# STM32_microcontroller_power.net
KiCad netlist of a schematic drawn in Altium Designer
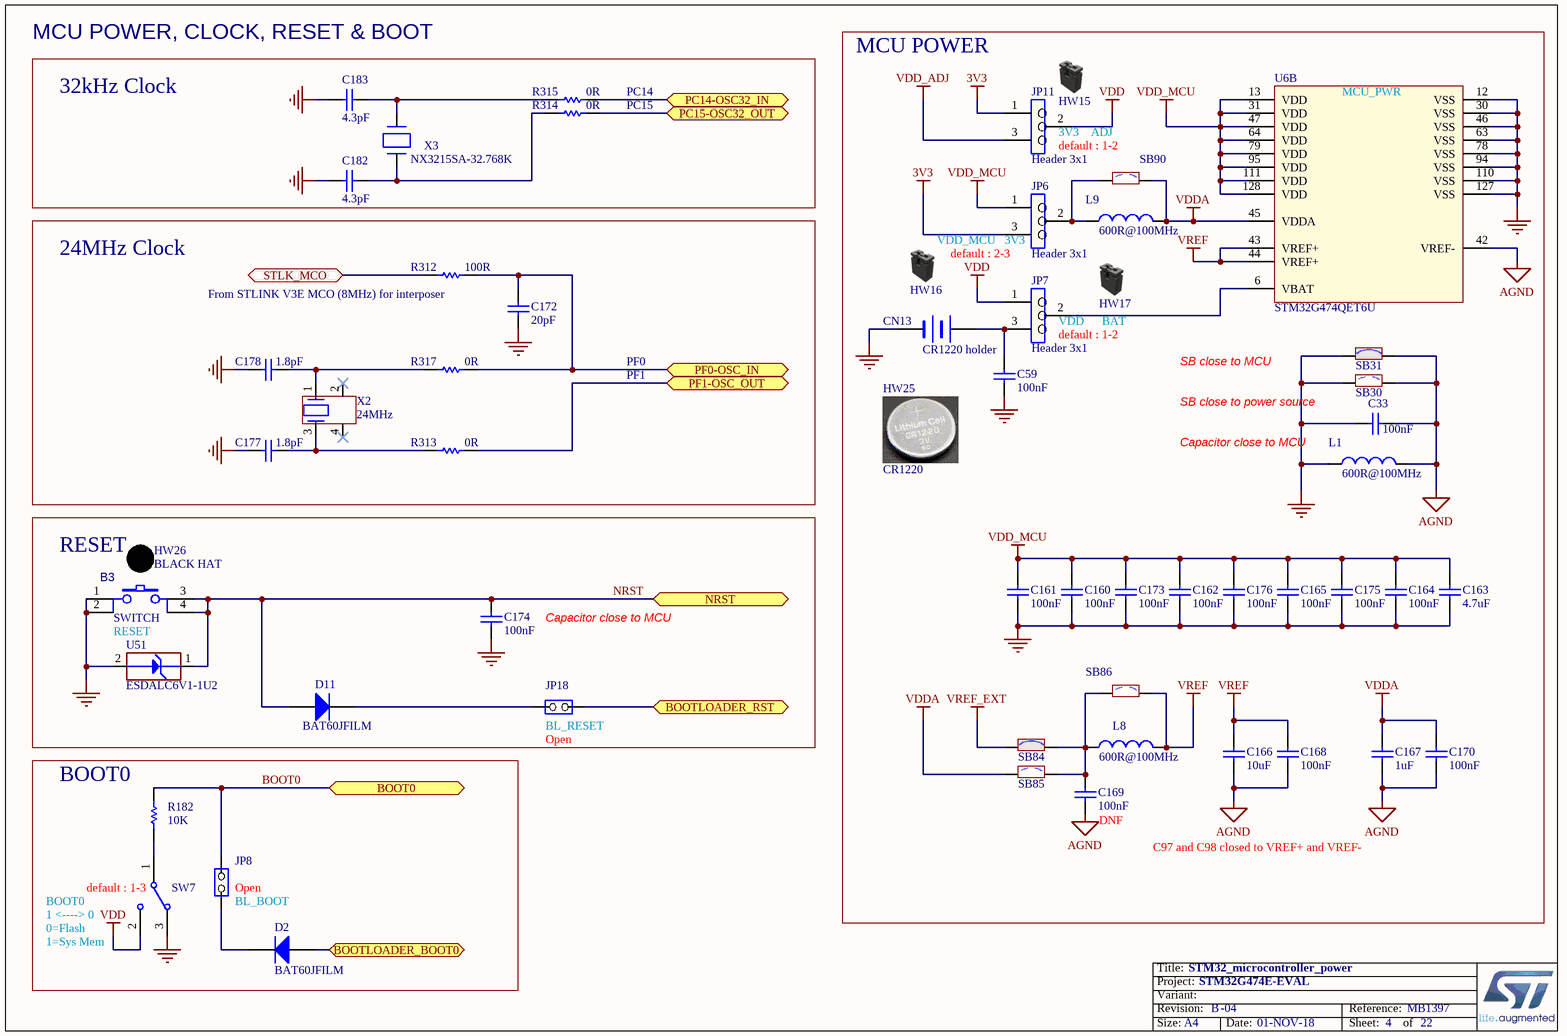
[diagram p0: STM32_microcontroller_power.SchDoc]

(export (version "E")
  (design (tool "Eeschema 10.0.6"))
  (components
    (comp (ref "B3")
      (value "SWITCH")
      (footprint "SWI_WEALTHMETAL_TD-0341_4P_BLACK")
      (description "Non-Open Push-Button 0.1A 24V BLACK")
      (fields
        (field (name "INTERNAL_PART_NUMBER") "MCD-00001")
        (field (name "MANUFACTURER_PART_NUMBER") "TD-0341")
        (field (name "PROVIDED_BY") "SUBCO")
      )
      (libsource (lib "MCD_PARTS_database") (part "SW-PUSH-CMS"))
    )
    (comp (ref "C33")
      (value "100nF")
      (footprint "C0402")
      (description "Capacitor, MLCC, 100nF, 16V, X7R, 10%, 0402, T=0.5mm")
      (fields
        (field (name "INTERNAL_PART_NUMBER") "MCD-00006")
        (field (name "MANUFACTURER_PART_NUMBER") "CC0402KRX7R7BB104")
        (field (name "PROVIDED_BY") "SUBCO")
      )
      (libsource (lib "MCD_PARTS_database") (part "Capacitor"))
    )
    (comp (ref "C59")
      (value "100nF")
      (footprint "C0402")
      (description "Capacitor, MLCC, 100nF, 16V, X7R, 10%, 0402, T=0.5mm")
      (fields
        (field (name "INTERNAL_PART_NUMBER") "MCD-00006")
        (field (name "MANUFACTURER_PART_NUMBER") "CC0402KRX7R7BB104")
        (field (name "PROVIDED_BY") "SUBCO")
      )
      (libsource (lib "MCD_PARTS_database") (part "Capacitor"))
    )
    (comp (ref "C160")
      (value "100nF")
      (footprint "C0402")
      (description "Capacitor, MLCC, 100nF, 16V, X7R, 10%, 0402, T=0.5mm")
      (fields
        (field (name "INTERNAL_PART_NUMBER") "MCD-00006")
        (field (name "MANUFACTURER_PART_NUMBER") "CC0402KRX7R7BB104")
        (field (name "PROVIDED_BY") "SUBCO")
      )
      (libsource (lib "MCD_PARTS_database") (part "Capacitor"))
    )
    (comp (ref "C161")
      (value "100nF")
      (footprint "C0402")
      (description "Capacitor, MLCC, 100nF, 16V, X7R, 10%, 0402, T=0.5mm")
      (fields
        (field (name "INTERNAL_PART_NUMBER") "MCD-00006")
        (field (name "MANUFACTURER_PART_NUMBER") "CC0402KRX7R7BB104")
        (field (name "PROVIDED_BY") "SUBCO")
      )
      (libsource (lib "MCD_PARTS_database") (part "Capacitor"))
    )
    (comp (ref "C162")
      (value "100nF")
      (footprint "C0402")
      (description "Capacitor, MLCC, 100nF, 16V, X7R, 10%, 0402, T=0.5mm")
      (fields
        (field (name "INTERNAL_PART_NUMBER") "MCD-00006")
        (field (name "MANUFACTURER_PART_NUMBER") "CC0402KRX7R7BB104")
        (field (name "PROVIDED_BY") "SUBCO")
      )
      (libsource (lib "MCD_PARTS_database") (part "Capacitor"))
    )
    (comp (ref "C163")
      (value "4.7uF")
      (footprint "C0603")
      (description "Capacitor, MLCC, 4.7uF, 16V, X5R, 10%, 0603, T=0.8mm")
      (fields
        (field (name "INTERNAL_PART_NUMBER") "MCD-00009")
        (field (name "MANUFACTURER_PART_NUMBER") "CC0603KRX5R7BB475")
        (field (name "PROVIDED_BY") "SUBCO")
      )
      (libsource (lib "MCD_PARTS_database") (part "Capacitor"))
    )
    (comp (ref "C164")
      (value "100nF")
      (footprint "C0402")
      (description "Capacitor, MLCC, 100nF, 16V, X7R, 10%, 0402, T=0.5mm")
      (fields
        (field (name "INTERNAL_PART_NUMBER") "MCD-00006")
        (field (name "MANUFACTURER_PART_NUMBER") "CC0402KRX7R7BB104")
        (field (name "PROVIDED_BY") "SUBCO")
      )
      (libsource (lib "MCD_PARTS_database") (part "Capacitor"))
    )
    (comp (ref "C165")
      (value "100nF")
      (footprint "C0402")
      (description "Capacitor, MLCC, 100nF, 16V, X7R, 10%, 0402, T=0.5mm")
      (fields
        (field (name "INTERNAL_PART_NUMBER") "MCD-00006")
        (field (name "MANUFACTURER_PART_NUMBER") "CC0402KRX7R7BB104")
        (field (name "PROVIDED_BY") "SUBCO")
      )
      (libsource (lib "MCD_PARTS_database") (part "Capacitor"))
    )
    (comp (ref "C166")
      (value "10uF")
      (footprint "C0805")
      (description "Capacitor, MLCC, 10uF, 25V, X5R, 10%, 0805, T=0,85mm")
      (fields
        (field (name "INTERNAL_PART_NUMBER") "MCD-00014")
        (field (name "MANUFACTURER_PART_NUMBER") "CC0805KRX5R8BB106")
        (field (name "PROVIDED_BY") "SUBCO")
      )
      (libsource (lib "MCD_PARTS_database") (part "Capacitor"))
    )
    (comp (ref "C167")
      (value "1uF")
      (footprint "C0603")
      (description "Capacitor, MLCC, 1uF, 16V, X5R, 10%, 0603, T=0,8mm")
      (fields
        (field (name "INTERNAL_PART_NUMBER") "MCD-00010")
        (field (name "MANUFACTURER_PART_NUMBER") "CC0603KRX5R7BB105")
        (field (name "PROVIDED_BY") "SUBCO")
      )
      (libsource (lib "MCD_PARTS_database") (part "Capacitor"))
    )
    (comp (ref "C168")
      (value "100nF")
      (footprint "C0402")
      (description "Capacitor, MLCC, 100nF, 16V, X7R, 10%, 0402, T=0.5mm")
      (fields
        (field (name "INTERNAL_PART_NUMBER") "MCD-00006")
        (field (name "MANUFACTURER_PART_NUMBER") "CC0402KRX7R7BB104")
        (field (name "PROVIDED_BY") "SUBCO")
      )
      (libsource (lib "MCD_PARTS_database") (part "Capacitor"))
    )
    (comp (ref "C169")
      (value "100nF")
      (footprint "C0402")
      (description "Capacitor, MLCC, 100nF, 16V, X7R, 10%, 0402, T=0.5mm")
      (fields
        (field (name "INTERNAL_PART_NUMBER") "MCD-00006")
        (field (name "MANUFACTURER_PART_NUMBER") "CC0402KRX7R7BB104")
        (field (name "PROVIDED_BY") "SUBCO")
      )
      (libsource (lib "MCD_PARTS_database") (part "Capacitor"))
    )
    (comp (ref "C170")
      (value "100nF")
      (footprint "C0402")
      (description "Capacitor, MLCC, 100nF, 16V, X7R, 10%, 0402, T=0.5mm")
      (fields
        (field (name "INTERNAL_PART_NUMBER") "MCD-00006")
        (field (name "MANUFACTURER_PART_NUMBER") "CC0402KRX7R7BB104")
        (field (name "PROVIDED_BY") "SUBCO")
      )
      (libsource (lib "MCD_PARTS_database") (part "Capacitor"))
    )
    (comp (ref "C172")
      (value "20pF")
      (footprint "C0402")
      (description "Capacitor, MLCC, 20pF, 50V, NPO, 5%, 0402, T=0,5mm")
      (fields
        (field (name "INTERNAL_PART_NUMBER") "MCD-00016")
        (field (name "MANUFACTURER_PART_NUMBER") "CC0402JRNPO9BN200")
        (field (name "PROVIDED_BY") "SUBCO")
      )
      (libsource (lib "MCD_PARTS_database") (part "Capacitor"))
    )
    (comp (ref "C173")
      (value "100nF")
      (footprint "C0402")
      (description "Capacitor, MLCC, 100nF, 16V, X7R, 10%, 0402, T=0.5mm")
      (fields
        (field (name "INTERNAL_PART_NUMBER") "MCD-00006")
        (field (name "MANUFACTURER_PART_NUMBER") "CC0402KRX7R7BB104")
        (field (name "PROVIDED_BY") "SUBCO")
      )
      (libsource (lib "MCD_PARTS_database") (part "Capacitor"))
    )
    (comp (ref "C174")
      (value "100nF")
      (footprint "C0402")
      (description "Capacitor, MLCC, 100nF, 16V, X7R, 10%, 0402, T=0.5mm")
      (fields
        (field (name "INTERNAL_PART_NUMBER") "MCD-00006")
        (field (name "MANUFACTURER_PART_NUMBER") "CC0402KRX7R7BB104")
        (field (name "PROVIDED_BY") "SUBCO")
      )
      (libsource (lib "MCD_PARTS_database") (part "Capacitor"))
    )
    (comp (ref "C175")
      (value "100nF")
      (footprint "C0402")
      (description "Capacitor, MLCC, 100nF, 16V, X7R, 10%, 0402, T=0.5mm")
      (fields
        (field (name "INTERNAL_PART_NUMBER") "MCD-00006")
        (field (name "MANUFACTURER_PART_NUMBER") "CC0402KRX7R7BB104")
        (field (name "PROVIDED_BY") "SUBCO")
      )
      (libsource (lib "MCD_PARTS_database") (part "Capacitor"))
    )
    (comp (ref "C176")
      (value "100nF")
      (footprint "C0402")
      (description "Capacitor, MLCC, 100nF, 16V, X7R, 10%, 0402, T=0.5mm")
      (fields
        (field (name "INTERNAL_PART_NUMBER") "MCD-00006")
        (field (name "MANUFACTURER_PART_NUMBER") "CC0402KRX7R7BB104")
        (field (name "PROVIDED_BY") "SUBCO")
      )
      (libsource (lib "MCD_PARTS_database") (part "Capacitor"))
    )
    (comp (ref "C177")
      (value "1.8pF")
      (footprint "C0402")
      (description "Capacitor, MLCC, 1.8pF, 50V, NPO, +-0.25pF, 0402, T=0,5mm")
      (fields
        (field (name "INTERNAL_PART_NUMBER") "MCD-01598")
        (field (name "MANUFACTURER_PART_NUMBER") "CC0402CRNPO9BN1R8")
        (field (name "PROVIDED_BY") "SUBCO")
      )
      (libsource (lib "MCD_PARTS_database") (part "Capacitor"))
    )
    (comp (ref "C178")
      (value "1.8pF")
      (footprint "C0402")
      (description "Capacitor, MLCC, 1.8pF, 50V, NPO, +-0.25pF, 0402, T=0,5mm")
      (fields
        (field (name "INTERNAL_PART_NUMBER") "MCD-01598")
        (field (name "MANUFACTURER_PART_NUMBER") "CC0402CRNPO9BN1R8")
        (field (name "PROVIDED_BY") "SUBCO")
      )
      (libsource (lib "MCD_PARTS_database") (part "Capacitor"))
    )
    (comp (ref "C182")
      (value "4.3pF")
      (footprint "C0402")
      (description "Capacitor, MLCC, 4.3pF, 50V, NPO, +-0.25pF, 0402, T=0,5mm")
      (fields
        (field (name "INTERNAL_PART_NUMBER") "MCD-01706")
        (field (name "MANUFACTURER_PART_NUMBER") "CC0402CRNPO9BN4R3")
        (field (name "PROVIDED_BY") "SUBCO")
      )
      (libsource (lib "MCD_PARTS_database") (part "Capacitor"))
    )
    (comp (ref "C183")
      (value "4.3pF")
      (footprint "C0402")
      (description "Capacitor, MLCC, 4.3pF, 50V, NPO, +-0.25pF, 0402, T=0,5mm")
      (fields
        (field (name "INTERNAL_PART_NUMBER") "MCD-01706")
        (field (name "MANUFACTURER_PART_NUMBER") "CC0402CRNPO9BN4R3")
        (field (name "PROVIDED_BY") "SUBCO")
      )
      (libsource (lib "MCD_PARTS_database") (part "Capacitor"))
    )
    (comp (ref "CN13")
      (value "CR1220 holder")
      (footprint "BAT_HARWIN_S8411-45R_SMD_2P")
      (description "Battery Coin Cell holder, CR1220_12mm, Height 4.25mm")
      (fields
        (field (name "INTERNAL_PART_NUMBER") "MCD-00558")
        (field (name "MANUFACTURER_PART_NUMBER") "S8411-45R")
        (field (name "PROVIDED_BY") "SUBCO")
      )
      (libsource (lib "MCD_PARTS_database") (part "BATTERY HOLDER"))
    )
    (comp (ref "D2")
      (value "BAT60JFILM")
      (footprint "DIO_SOD323")
      (fields
        (field (name "INTERNAL_PART_NUMBER") "MCD-00034")
        (field (name "MANUFACTURER") "STMICROELECTRONICS")
        (field (name "BMS_PART_NUMBER") "9151097")
        (field (name "PROVIDED_BY") "SUBCO with ST control")
      )
      (libsource (lib "MCD_PARTS_database") (part "BAT60JFILM"))
    )
    (comp (ref "D11")
      (value "BAT60JFILM")
      (footprint "DIO_SOD323")
      (fields
        (field (name "INTERNAL_PART_NUMBER") "MCD-00034")
        (field (name "MANUFACTURER") "STMICROELECTRONICS")
        (field (name "BMS_PART_NUMBER") "9151097")
        (field (name "PROVIDED_BY") "SUBCO with ST control")
      )
      (libsource (lib "MCD_PARTS_database") (part "BAT60JFILM"))
    )
    (comp (ref "HW15")
      (value "Shunt Black 2.54mm")
      (description "SHUNT 2.54mm BLACK")
      (fields
        (field (name "INTERNAL_PART_NUMBER") "MCD-00043")
        (field (name "MANUFACTURER_PART_NUMBER") "SNT-100-BK-G")
        (field (name "PROVIDED_BY") "SUBCO")
      )
      (libsource (lib "MCD_PARTS_database") (part "Shunt Black 2.54mm"))
    )
    (comp (ref "HW16")
      (value "Shunt Black 2.54mm")
      (description "SHUNT 2.54mm BLACK")
      (fields
        (field (name "INTERNAL_PART_NUMBER") "MCD-00043")
        (field (name "MANUFACTURER_PART_NUMBER") "SNT-100-BK-G")
        (field (name "PROVIDED_BY") "SUBCO")
      )
      (libsource (lib "MCD_PARTS_database") (part "Shunt Black 2.54mm"))
    )
    (comp (ref "HW17")
      (value "Shunt Black 2.54mm")
      (description "SHUNT 2.54mm BLACK")
      (fields
        (field (name "INTERNAL_PART_NUMBER") "MCD-00043")
        (field (name "MANUFACTURER_PART_NUMBER") "SNT-100-BK-G")
        (field (name "PROVIDED_BY") "SUBCO")
      )
      (libsource (lib "MCD_PARTS_database") (part "Shunt Black 2.54mm"))
    )
    (comp (ref "HW25")
      (value "CR1220")
      (description "Battery Back-Up CR1220,3V,12X2.0MM,35mA")
      (fields
        (field (name "INTERNAL_PART_NUMBER") "MCD-01197")
        (field (name "MANUFACTURER") "tbd")
        (field (name "PROVIDED_BY") "SUBCO")
      )
      (libsource (lib "MCD_PARTS_database") (part "BBU_CR1220"))
    )
    (comp (ref "HW26")
      (value "BLACK HAT")
      (description "Black Hat for switch TD0341X-G01-BLA")
      (fields
        (field (name "INTERNAL_PART_NUMBER") "MCD-00635")
        (field (name "MANUFACTURER_PART_NUMBER") "988.16.09.3.00003_SH-517")
        (field (name "PROVIDED_BY") "SUBCO")
      )
      (libsource (lib "MCD_PARTS_database") (part "BUTTON_HAT_BLACK"))
    )
    (comp (ref "JP6")
      (value "Header 3x1")
      (footprint "CON_SAMTEC_TSW-103-07-F-S")
      (description "Header, 3x1, 2,54mm, VR, TH, Height 5.84mm/2.54mm")
      (fields
        (field (name "INTERNAL_PART_NUMBER") "MCD-00111")
        (field (name "MANUFACTURER_PART_NUMBER") "TSW-103-07-F-S")
        (field (name "PROVIDED_BY") "SUBCO")
      )
      (libsource (lib "MCD_PARTS_database") (part "Jumper_Header 3x1"))
    )
    (comp (ref "JP7")
      (value "Header 3x1")
      (footprint "CON_SAMTEC_TSW-103-07-F-S")
      (description "Header, 3x1, 2,54mm, VR, TH, Height 5.84mm/2.54mm")
      (fields
        (field (name "INTERNAL_PART_NUMBER") "MCD-00111")
        (field (name "MANUFACTURER_PART_NUMBER") "TSW-103-07-F-S")
        (field (name "PROVIDED_BY") "SUBCO")
      )
      (libsource (lib "MCD_PARTS_database") (part "Jumper_Header 3x1"))
    )
    (comp (ref "JP8")
      (value "Jumper_Header 2x1")
      (footprint "CON_SAMTEC_TSW-102-07-G-S")
      (description "Header, 2x1, 2,54mm, VR, TH, Height 5.84mm/2.54mm")
      (fields
        (field (name "INTERNAL_PART_NUMBER") "MCD-00045")
        (field (name "MANUFACTURER_PART_NUMBER") "TSW-102-07-x-S")
        (field (name "PROVIDED_BY") "SUBCO")
      )
      (libsource (lib "MCD_PARTS_database") (part "Jumper_Header 2x1"))
    )
    (comp (ref "JP11")
      (value "Header 3x1")
      (footprint "CON_SAMTEC_TSW-103-07-F-S")
      (description "Header, 3x1, 2,54mm, VR, TH, Height 5.84mm/2.54mm")
      (fields
        (field (name "INTERNAL_PART_NUMBER") "MCD-00111")
        (field (name "MANUFACTURER_PART_NUMBER") "TSW-103-07-F-S")
        (field (name "PROVIDED_BY") "SUBCO")
      )
      (libsource (lib "MCD_PARTS_database") (part "Jumper_Header 3x1"))
    )
    (comp (ref "JP18")
      (value "Jumper_Header 2x1")
      (footprint "CON_SAMTEC_TSW-102-07-G-S")
      (description "Header, 2x1, 2,54mm, VR, TH, Height 5.84mm/2.54mm")
      (fields
        (field (name "INTERNAL_PART_NUMBER") "MCD-00045")
        (field (name "MANUFACTURER_PART_NUMBER") "TSW-102-07-x-S")
        (field (name "PROVIDED_BY") "SUBCO")
      )
      (libsource (lib "MCD_PARTS_database") (part "Jumper_Header 2x1"))
    )
    (comp (ref "L1")
      (value "600R@100MHz")
      (footprint "L0603")
      (description "SMD Chip ferrite bead, 600R@100MHz +/-25%, 350mA, 500mohm DC, 0603, T=0.8mm")
      (fields
        (field (name "INTERNAL_PART_NUMBER") "MCD-00047")
        (field (name "MANUFACTURER_PART_NUMBER") "FCM1608KF-601T03")
        (field (name "PROVIDED_BY") "SUBCO")
      )
      (libsource (lib "MCD_PARTS_database") (part "BEAD"))
    )
    (comp (ref "L8")
      (value "600R@100MHz")
      (footprint "L0603")
      (description "SMD Chip ferrite bead, 600R@100MHz +/-25%, 350mA, 500mohm DC, 0603, T=0.8mm")
      (fields
        (field (name "INTERNAL_PART_NUMBER") "MCD-00047")
        (field (name "MANUFACTURER_PART_NUMBER") "FCM1608KF-601T03")
        (field (name "PROVIDED_BY") "SUBCO")
      )
      (libsource (lib "MCD_PARTS_database") (part "BEAD"))
    )
    (comp (ref "L9")
      (value "600R@100MHz")
      (footprint "L0603")
      (description "SMD Chip ferrite bead, 600R@100MHz +/-25%, 350mA, 500mohm DC, 0603, T=0.8mm")
      (fields
        (field (name "INTERNAL_PART_NUMBER") "MCD-00047")
        (field (name "MANUFACTURER_PART_NUMBER") "FCM1608KF-601T03")
        (field (name "PROVIDED_BY") "SUBCO")
      )
      (libsource (lib "MCD_PARTS_database") (part "BEAD"))
    )
    (comp (ref "R182")
      (value "10K")
      (footprint "R0402")
      (description "Resistor,10K,0402,1%,1/16W")
      (fields
        (field (name "INTERNAL_PART_NUMBER") "MCD-00053")
        (field (name "MANUFACTURER_PART_NUMBER") "RC0402FR-0710KL")
        (field (name "PROVIDED_BY") "SUBCO")
      )
      (libsource (lib "MCD_PARTS_database") (part "Resistor"))
    )
    (comp (ref "R312")
      (value "100R")
      (footprint "R0402")
      (description "Resistor,100R,0402,1%,1/16W")
      (fields
        (field (name "INTERNAL_PART_NUMBER") "MCD-00119")
        (field (name "MANUFACTURER_PART_NUMBER") "RC0402FR-07100RL")
        (field (name "PROVIDED_BY") "SUBCO")
      )
      (libsource (lib "MCD_PARTS_database") (part "Resistor"))
    )
    (comp (ref "R313")
      (value "0R")
      (footprint "R0402")
      (description "Resistor,0R,0402,5%,1/16W")
      (fields
        (field (name "INTERNAL_PART_NUMBER") "MCD-00052")
        (field (name "MANUFACTURER_PART_NUMBER") "RC0402JR-070RL")
        (field (name "PROVIDED_BY") "SUBCO")
      )
      (libsource (lib "MCD_PARTS_database") (part "Resistor"))
    )
    (comp (ref "R314")
      (value "0R")
      (footprint "R0402")
      (description "Resistor,0R,0402,5%,1/16W")
      (fields
        (field (name "INTERNAL_PART_NUMBER") "MCD-00052")
        (field (name "MANUFACTURER_PART_NUMBER") "RC0402JR-070RL")
        (field (name "PROVIDED_BY") "SUBCO")
      )
      (libsource (lib "MCD_PARTS_database") (part "Resistor"))
    )
    (comp (ref "R315")
      (value "0R")
      (footprint "R0402")
      (description "Resistor,0R,0402,5%,1/16W")
      (fields
        (field (name "INTERNAL_PART_NUMBER") "MCD-00052")
        (field (name "MANUFACTURER_PART_NUMBER") "RC0402JR-070RL")
        (field (name "PROVIDED_BY") "SUBCO")
      )
      (libsource (lib "MCD_PARTS_database") (part "Resistor"))
    )
    (comp (ref "R317")
      (value "0R")
      (footprint "R0402")
      (description "Resistor,0R,0402,5%,1/16W")
      (fields
        (field (name "INTERNAL_PART_NUMBER") "MCD-00052")
        (field (name "MANUFACTURER_PART_NUMBER") "RC0402JR-070RL")
        (field (name "PROVIDED_BY") "SUBCO")
      )
      (libsource (lib "MCD_PARTS_database") (part "Resistor"))
    )
    (comp (ref "SB30")
      (value "SB_OFF")
      (footprint "SOLDER-BRIDGE_R0603-0R")
      (description "Solder Bridge OFF")
      (fields
        (field (name "INTERNAL_PART_NUMBER") "MCD-00072")
        (field (name "MANUFACTURER_PART_NUMBER") "RC0603JR-070RL")
        (field (name "PROVIDED_BY") "SUBCO")
      )
      (libsource (lib "MCD_PARTS_database") (part "SB_OFF"))
    )
    (comp (ref "SB31")
      (value "SB_ON")
      (footprint "SOLDER-BRIDGE_R0603-0R")
      (description "Solder Bridge ON")
      (fields
        (field (name "INTERNAL_PART_NUMBER") "MCD-00071")
        (field (name "MANUFACTURER_PART_NUMBER") "RC0603JR-070RL")
        (field (name "PROVIDED_BY") "SUBCO")
      )
      (libsource (lib "MCD_PARTS_database") (part "SB_ON"))
    )
    (comp (ref "SB84")
      (value "SB_ON")
      (footprint "SOLDER-BRIDGE_R0603-0R")
      (description "Solder Bridge ON")
      (fields
        (field (name "INTERNAL_PART_NUMBER") "MCD-00071")
        (field (name "MANUFACTURER_PART_NUMBER") "RC0603JR-070RL")
        (field (name "PROVIDED_BY") "SUBCO")
      )
      (libsource (lib "MCD_PARTS_database") (part "SB_ON"))
    )
    (comp (ref "SB85")
      (value "SB_OFF")
      (footprint "SOLDER-BRIDGE_R0603-0R")
      (description "Solder Bridge OFF")
      (fields
        (field (name "INTERNAL_PART_NUMBER") "MCD-00072")
        (field (name "MANUFACTURER_PART_NUMBER") "RC0603JR-070RL")
        (field (name "PROVIDED_BY") "SUBCO")
      )
      (libsource (lib "MCD_PARTS_database") (part "SB_OFF"))
    )
    (comp (ref "SB86")
      (value "SB_OFF")
      (footprint "SOLDER-BRIDGE_R0603-0R")
      (description "Solder Bridge OFF")
      (fields
        (field (name "INTERNAL_PART_NUMBER") "MCD-00072")
        (field (name "MANUFACTURER_PART_NUMBER") "RC0603JR-070RL")
        (field (name "PROVIDED_BY") "SUBCO")
      )
      (libsource (lib "MCD_PARTS_database") (part "SB_OFF"))
    )
    (comp (ref "SB90")
      (value "SB_OFF")
      (footprint "SOLDER-BRIDGE_R0603-0R")
      (description "Solder Bridge OFF")
      (fields
        (field (name "INTERNAL_PART_NUMBER") "MCD-00072")
        (field (name "MANUFACTURER_PART_NUMBER") "RC0603JR-070RL")
        (field (name "PROVIDED_BY") "SUBCO")
      )
      (libsource (lib "MCD_PARTS_database") (part "SB_OFF"))
    )
    (comp (ref "SW7")
      (value "SW_MECA_1K2")
      (footprint "SWI_EAO_09-03290-01_EXTENDED_STRAIGHT_BLACK")
      (description "Mechanical Slide Switches 1K2 BLK ACT GOLD STRT MNT")
      (fields
        (field (name "INTERNAL_PART_NUMBER") "MCD-00566")
        (field (name "MANUFACTURER_PART_NUMBER") "09.03290.01")
        (field (name "PROVIDED_BY") "SUBCO")
      )
      (libsource (lib "MCD_PARTS_database") (part "SW_MECA_1K2"))
    )
    (comp (ref "U6")
      (value "STM32G474QET6U")
      (footprint "ICC_LQFP128_14X14_P040")
      (fields
        (field (name "INTERNAL_PART_NUMBER") "MCD-01707")
        (field (name "MANUFACTURER") "STMICROELECTRONICS")
        (field (name "PROVIDED_BY") "SUBCO with ST control")
      )
      (libsource (lib "MCD_PARTS_database") (part "STM32G474WET6"))
    )
    (comp (ref "U51")
      (value "ESDALC6V1-1U2")
      (footprint "ESD_ST0201")
      (description "ESD protection 6V1")
      (fields
        (field (name "INTERNAL_PART_NUMBER") "MCD-00170")
        (field (name "MANUFACTURER") "STMICROELECTRONICS")
        (field (name "PROVIDED_BY") "SUBCO with ST control")
      )
      (libsource (lib "MCD_PARTS_database") (part "ESD-TRANSIL"))
    )
    (comp (ref "X2")
      (value "24MHz")
      (footprint "CRY_NX2016SA_4P")
      (description "24MHz crystal oscillator - Cl:6pf -")
      (fields
        (field (name "INTERNAL_PART_NUMBER") "MCD-01036")
        (field (name "MANUFACTURER_PART_NUMBER") "NX2016SA 24MHz EXS00A-CS10820")
      )
      (libsource (lib "MCD_PARTS_database") (part "XTAL_4_PINS"))
    )
    (comp (ref "X3")
      (value "NX3215SA-32.768K")
      (footprint "CRY_NX3215SA_2P")
      (description "Crystal 32.768kHz, 6pF, -+20PPM, R=50K, SMD")
      (fields
        (field (name "INTERNAL_PART_NUMBER") "MCD-00091")
        (field (name "MANUFACTURER_PART_NUMBER") "NX3215SA 32.768KHz EXS00A-MU00525")
      )
      (libsource (lib "MCD_PARTS_database") (part "XTAL_2_PINS"))
    )
  )
  (nets
    (net (code "1") (name "/BOOT0") (class "Default")
      (node (ref "JP8") (pin "2") (pinfunction "NO_2") (pintype "passive"))
      (node (ref "R182") (pin "1") (pinfunction "1_1") (pintype "passive"))
    )
    (net (code "2") (name "/BOOTLOADER_BOOT0") (class "Default")
      (node (ref "D2") (pin "1") (pinfunction "A_1") (pintype "passive"))
    )
    (net (code "3") (name "/BOOTLOADER_RST") (class "Default")
      (node (ref "JP18") (pin "2") (pinfunction "NO_2") (pintype "passive"))
    )
    (net (code "4") (name "/NRST") (class "Default")
      (node (ref "B3") (pin "3") (pinfunction "3_3") (pintype "passive"))
      (node (ref "B3") (pin "4") (pinfunction "4_4") (pintype "passive"))
      (node (ref "C174") (pin "2") (pinfunction "2_2") (pintype "passive"))
      (node (ref "D11") (pin "1") (pinfunction "A_1") (pintype "passive"))
      (node (ref "U51") (pin "1") (pinfunction "IO1_1") (pintype "passive"))
    )
    (net (code "5") (name "/PC14-OSC32_IN") (class "Default")
      (node (ref "R315") (pin "2") (pinfunction "2_2") (pintype "passive"))
    )
    (net (code "6") (name "/PC15-OSC32_OUT") (class "Default")
      (node (ref "R314") (pin "2") (pinfunction "2_2") (pintype "passive"))
    )
    (net (code "7") (name "/PF0-OSC_IN") (class "Default")
      (node (ref "C172") (pin "1") (pinfunction "1_1") (pintype "passive"))
      (node (ref "R312") (pin "2") (pinfunction "2_2") (pintype "passive"))
      (node (ref "R317") (pin "2") (pinfunction "2_2") (pintype "passive"))
    )
    (net (code "8") (name "/PF1-OSC_OUT") (class "Default")
      (node (ref "R313") (pin "2") (pinfunction "2_2") (pintype "passive"))
    )
    (net (code "9") (name "/STLK_MCO") (class "Default")
      (node (ref "R312") (pin "1") (pinfunction "1_1") (pintype "passive"))
    )
    (net (code "10") (name "3V3") (class "Default")
      (node (ref "JP11") (pin "1") (pinfunction "1_1") (pintype "passive"))
      (node (ref "JP6") (pin "3") (pinfunction "3_3") (pintype "passive"))
    )
    (net (code "11") (name "AGND") (class "Default")
      (node (ref "C166") (pin "1") (pinfunction "1_1") (pintype "passive"))
      (node (ref "C167") (pin "2") (pinfunction "2_2") (pintype "passive"))
      (node (ref "C168") (pin "1") (pinfunction "1_1") (pintype "passive"))
      (node (ref "C169") (pin "1") (pinfunction "1_1") (pintype "passive"))
      (node (ref "C170") (pin "1") (pinfunction "1_1") (pintype "passive"))
      (node (ref "C33") (pin "1") (pinfunction "1_1") (pintype "passive"))
      (node (ref "L1") (pin "2") (pinfunction "2_2") (pintype "passive"))
      (node (ref "SB30") (pin "2") (pinfunction "2_2") (pintype "passive"))
      (node (ref "SB31") (pin "2") (pinfunction "2_2") (pintype "passive"))
      (node (ref "U6") (pin "42") (pinfunction "VREF-_42") (pintype "passive"))
    )
    (net (code "12") (name "GND") (class "Default")
      (node (ref "B3") (pin "1") (pinfunction "1_1") (pintype "passive"))
      (node (ref "B3") (pin "2") (pinfunction "2_2") (pintype "passive"))
      (node (ref "C160") (pin "1") (pinfunction "1_1") (pintype "passive"))
      (node (ref "C161") (pin "1") (pinfunction "1_1") (pintype "passive"))
      (node (ref "C162") (pin "1") (pinfunction "1_1") (pintype "passive"))
      (node (ref "C163") (pin "2") (pinfunction "2_2") (pintype "passive"))
      (node (ref "C164") (pin "1") (pinfunction "1_1") (pintype "passive"))
      (node (ref "C165") (pin "1") (pinfunction "1_1") (pintype "passive"))
      (node (ref "C172") (pin "2") (pinfunction "2_2") (pintype "passive"))
      (node (ref "C173") (pin "1") (pinfunction "1_1") (pintype "passive"))
      (node (ref "C174") (pin "1") (pinfunction "1_1") (pintype "passive"))
      (node (ref "C175") (pin "1") (pinfunction "1_1") (pintype "passive"))
      (node (ref "C176") (pin "1") (pinfunction "1_1") (pintype "passive"))
      (node (ref "C177") (pin "1") (pinfunction "1_1") (pintype "passive"))
      (node (ref "C178") (pin "1") (pinfunction "1_1") (pintype "passive"))
      (node (ref "C182") (pin "1") (pinfunction "1_1") (pintype "passive"))
      (node (ref "C183") (pin "1") (pinfunction "1_1") (pintype "passive"))
      (node (ref "C33") (pin "2") (pinfunction "2_2") (pintype "passive"))
      (node (ref "C59") (pin "1") (pinfunction "1_1") (pintype "passive"))
      (node (ref "CN13") (pin "2") (pinfunction "-_2") (pintype "passive"))
      (node (ref "L1") (pin "1") (pinfunction "1_1") (pintype "passive"))
      (node (ref "SB30") (pin "1") (pinfunction "1_1") (pintype "passive"))
      (node (ref "SB31") (pin "1") (pinfunction "1_1") (pintype "passive"))
      (node (ref "SW7") (pin "3") (pintype "passive"))
      (node (ref "U51") (pin "2") (pinfunction "GND_2") (pintype "passive"))
      (node (ref "U6") (pin "110") (pinfunction "VSS_110") (pintype "passive"))
      (node (ref "U6") (pin "12") (pinfunction "VSS_12") (pintype "passive"))
      (node (ref "U6") (pin "127") (pinfunction "VSS_127") (pintype "passive"))
      (node (ref "U6") (pin "30") (pinfunction "VSS_30") (pintype "passive"))
      (node (ref "U6") (pin "46") (pinfunction "VSS_46") (pintype "passive"))
      (node (ref "U6") (pin "63") (pinfunction "VSS_63") (pintype "passive"))
      (node (ref "U6") (pin "78") (pinfunction "VSS_78") (pintype "passive"))
      (node (ref "U6") (pin "94") (pinfunction "VSS_94") (pintype "passive"))
    )
    (net (code "13") (name "Net-(C169-Pad2)") (class "Default")
      (node (ref "C169") (pin "2") (pinfunction "2_2") (pintype "passive"))
      (node (ref "L8") (pin "1") (pinfunction "1_1") (pintype "passive"))
      (node (ref "SB84") (pin "2") (pinfunction "2_2") (pintype "passive"))
      (node (ref "SB85") (pin "2") (pinfunction "2_2") (pintype "passive"))
      (node (ref "SB86") (pin "1") (pinfunction "1_1") (pintype "passive"))
    )
    (net (code "14") (name "Net-(C177-Pad2)") (class "Default")
      (node (ref "C177") (pin "2") (pinfunction "2_2") (pintype "passive"))
      (node (ref "R313") (pin "1") (pinfunction "1_1") (pintype "passive"))
      (node (ref "X2") (pin "3") (pinfunction "3_3") (pintype "passive"))
    )
    (net (code "15") (name "Net-(C178-Pad2)") (class "Default")
      (node (ref "C178") (pin "2") (pinfunction "2_2") (pintype "passive"))
      (node (ref "R317") (pin "1") (pinfunction "1_1") (pintype "passive"))
      (node (ref "X2") (pin "1") (pinfunction "1_1") (pintype "passive"))
    )
    (net (code "16") (name "Net-(CN13-+)") (class "Default")
      (node (ref "C59") (pin "2") (pinfunction "2_2") (pintype "passive"))
      (node (ref "CN13") (pin "1") (pinfunction "+_1") (pintype "passive"))
      (node (ref "JP7") (pin "3") (pinfunction "3_3") (pintype "passive"))
    )
    (net (code "17") (name "Net-(D2-K)") (class "Default")
      (node (ref "D2") (pin "2") (pinfunction "K_2") (pintype "passive"))
      (node (ref "JP8") (pin "1") (pinfunction "COMMON_1") (pintype "passive"))
    )
    (net (code "18") (name "Net-(D11-K)") (class "Default")
      (node (ref "D11") (pin "2") (pinfunction "K_2") (pintype "passive"))
      (node (ref "JP18") (pin "1") (pinfunction "COMMON_1") (pintype "passive"))
    )
    (net (code "19") (name "Net-(JP6-Pad2)") (class "Default")
      (node (ref "JP6") (pin "2") (pinfunction "2_2") (pintype "passive"))
      (node (ref "L9") (pin "1") (pinfunction "1_1") (pintype "passive"))
      (node (ref "SB90") (pin "1") (pinfunction "1_1") (pintype "passive"))
    )
    (net (code "20") (name "Net-(R182-Pad2)") (class "Default")
      (node (ref "R182") (pin "2") (pinfunction "2_2") (pintype "passive"))
      (node (ref "SW7") (pin "1") (pintype "passive"))
    )
    (net (code "21") (name "Net-(U6B-VBAT)") (class "Default")
      (node (ref "JP7") (pin "2") (pinfunction "2_2") (pintype "passive"))
      (node (ref "U6") (pin "6") (pinfunction "VBAT_6") (pintype "passive"))
    )
    (net (code "22") (name "Net-(X3-X1)") (class "Default")
      (node (ref "C182") (pin "2") (pinfunction "2_2") (pintype "passive"))
      (node (ref "R314") (pin "1") (pinfunction "1_1") (pintype "passive"))
      (node (ref "X3") (pin "1") (pinfunction "X1_1") (pintype "passive"))
    )
    (net (code "23") (name "Net-(X3-X2)") (class "Default")
      (node (ref "C183") (pin "2") (pinfunction "2_2") (pintype "passive"))
      (node (ref "R315") (pin "1") (pinfunction "1_1") (pintype "passive"))
      (node (ref "X3") (pin "2") (pinfunction "X2_2") (pintype "passive"))
    )
    (net (code "24") (name "VDD") (class "Default")
      (node (ref "JP11") (pin "2") (pinfunction "2_2") (pintype "passive"))
      (node (ref "JP7") (pin "1") (pinfunction "1_1") (pintype "passive"))
      (node (ref "SW7") (pin "2") (pintype "passive"))
    )
    (net (code "25") (name "VDDA") (class "Default")
      (node (ref "C167") (pin "1") (pinfunction "1_1") (pintype "passive"))
      (node (ref "C170") (pin "2") (pinfunction "2_2") (pintype "passive"))
      (node (ref "L9") (pin "2") (pinfunction "2_2") (pintype "passive"))
      (node (ref "SB85") (pin "1") (pinfunction "1_1") (pintype "passive"))
      (node (ref "SB90") (pin "2") (pinfunction "2_2") (pintype "passive"))
      (node (ref "U6") (pin "45") (pinfunction "VDDA_45") (pintype "passive"))
    )
    (net (code "26") (name "VDD_ADJ") (class "Default")
      (node (ref "JP11") (pin "3") (pinfunction "3_3") (pintype "passive"))
    )
    (net (code "27") (name "VDD_MCU") (class "Default")
      (node (ref "C160") (pin "2") (pinfunction "2_2") (pintype "passive"))
      (node (ref "C161") (pin "2") (pinfunction "2_2") (pintype "passive"))
      (node (ref "C162") (pin "2") (pinfunction "2_2") (pintype "passive"))
      (node (ref "C163") (pin "1") (pinfunction "1_1") (pintype "passive"))
      (node (ref "C164") (pin "2") (pinfunction "2_2") (pintype "passive"))
      (node (ref "C165") (pin "2") (pinfunction "2_2") (pintype "passive"))
      (node (ref "C173") (pin "2") (pinfunction "2_2") (pintype "passive"))
      (node (ref "C175") (pin "2") (pinfunction "2_2") (pintype "passive"))
      (node (ref "C176") (pin "2") (pinfunction "2_2") (pintype "passive"))
      (node (ref "JP6") (pin "1") (pinfunction "1_1") (pintype "passive"))
      (node (ref "U6") (pin "111") (pinfunction "VDD_111") (pintype "passive"))
      (node (ref "U6") (pin "128") (pinfunction "VDD_128") (pintype "passive"))
      (node (ref "U6") (pin "13") (pinfunction "VDD_13") (pintype "passive"))
      (node (ref "U6") (pin "31") (pinfunction "VDD_31") (pintype "passive"))
      (node (ref "U6") (pin "47") (pinfunction "VDD_47") (pintype "passive"))
      (node (ref "U6") (pin "64") (pinfunction "VDD_64") (pintype "passive"))
      (node (ref "U6") (pin "79") (pinfunction "VDD_79") (pintype "passive"))
      (node (ref "U6") (pin "95") (pinfunction "VDD_95") (pintype "passive"))
    )
    (net (code "28") (name "VREF") (class "Default")
      (node (ref "C166") (pin "2") (pinfunction "2_2") (pintype "passive"))
      (node (ref "C168") (pin "2") (pinfunction "2_2") (pintype "passive"))
      (node (ref "L8") (pin "2") (pinfunction "2_2") (pintype "passive"))
      (node (ref "SB86") (pin "2") (pinfunction "2_2") (pintype "passive"))
      (node (ref "U6") (pin "43") (pinfunction "VREF+_43") (pintype "passive"))
      (node (ref "U6") (pin "44") (pinfunction "VREF+_44") (pintype "passive"))
    )
    (net (code "29") (name "VREF_EXT") (class "Default")
      (node (ref "SB84") (pin "1") (pinfunction "1_1") (pintype "passive"))
    )
    (net (code "30") (name "unconnected-(X2-Pad2)") (class "Default")
      (node (ref "X2") (pin "2") (pinfunction "2_2") (pintype "passive+no_connect"))
    )
    (net (code "31") (name "unconnected-(X2-Pad4)") (class "Default")
      (node (ref "X2") (pin "4") (pinfunction "4_4") (pintype "passive+no_connect"))
    )
  )
)
